# LPCB220_-_REMOTE_ACCELS.net
KiCad netlist of a schematic drawn in Altium Designer
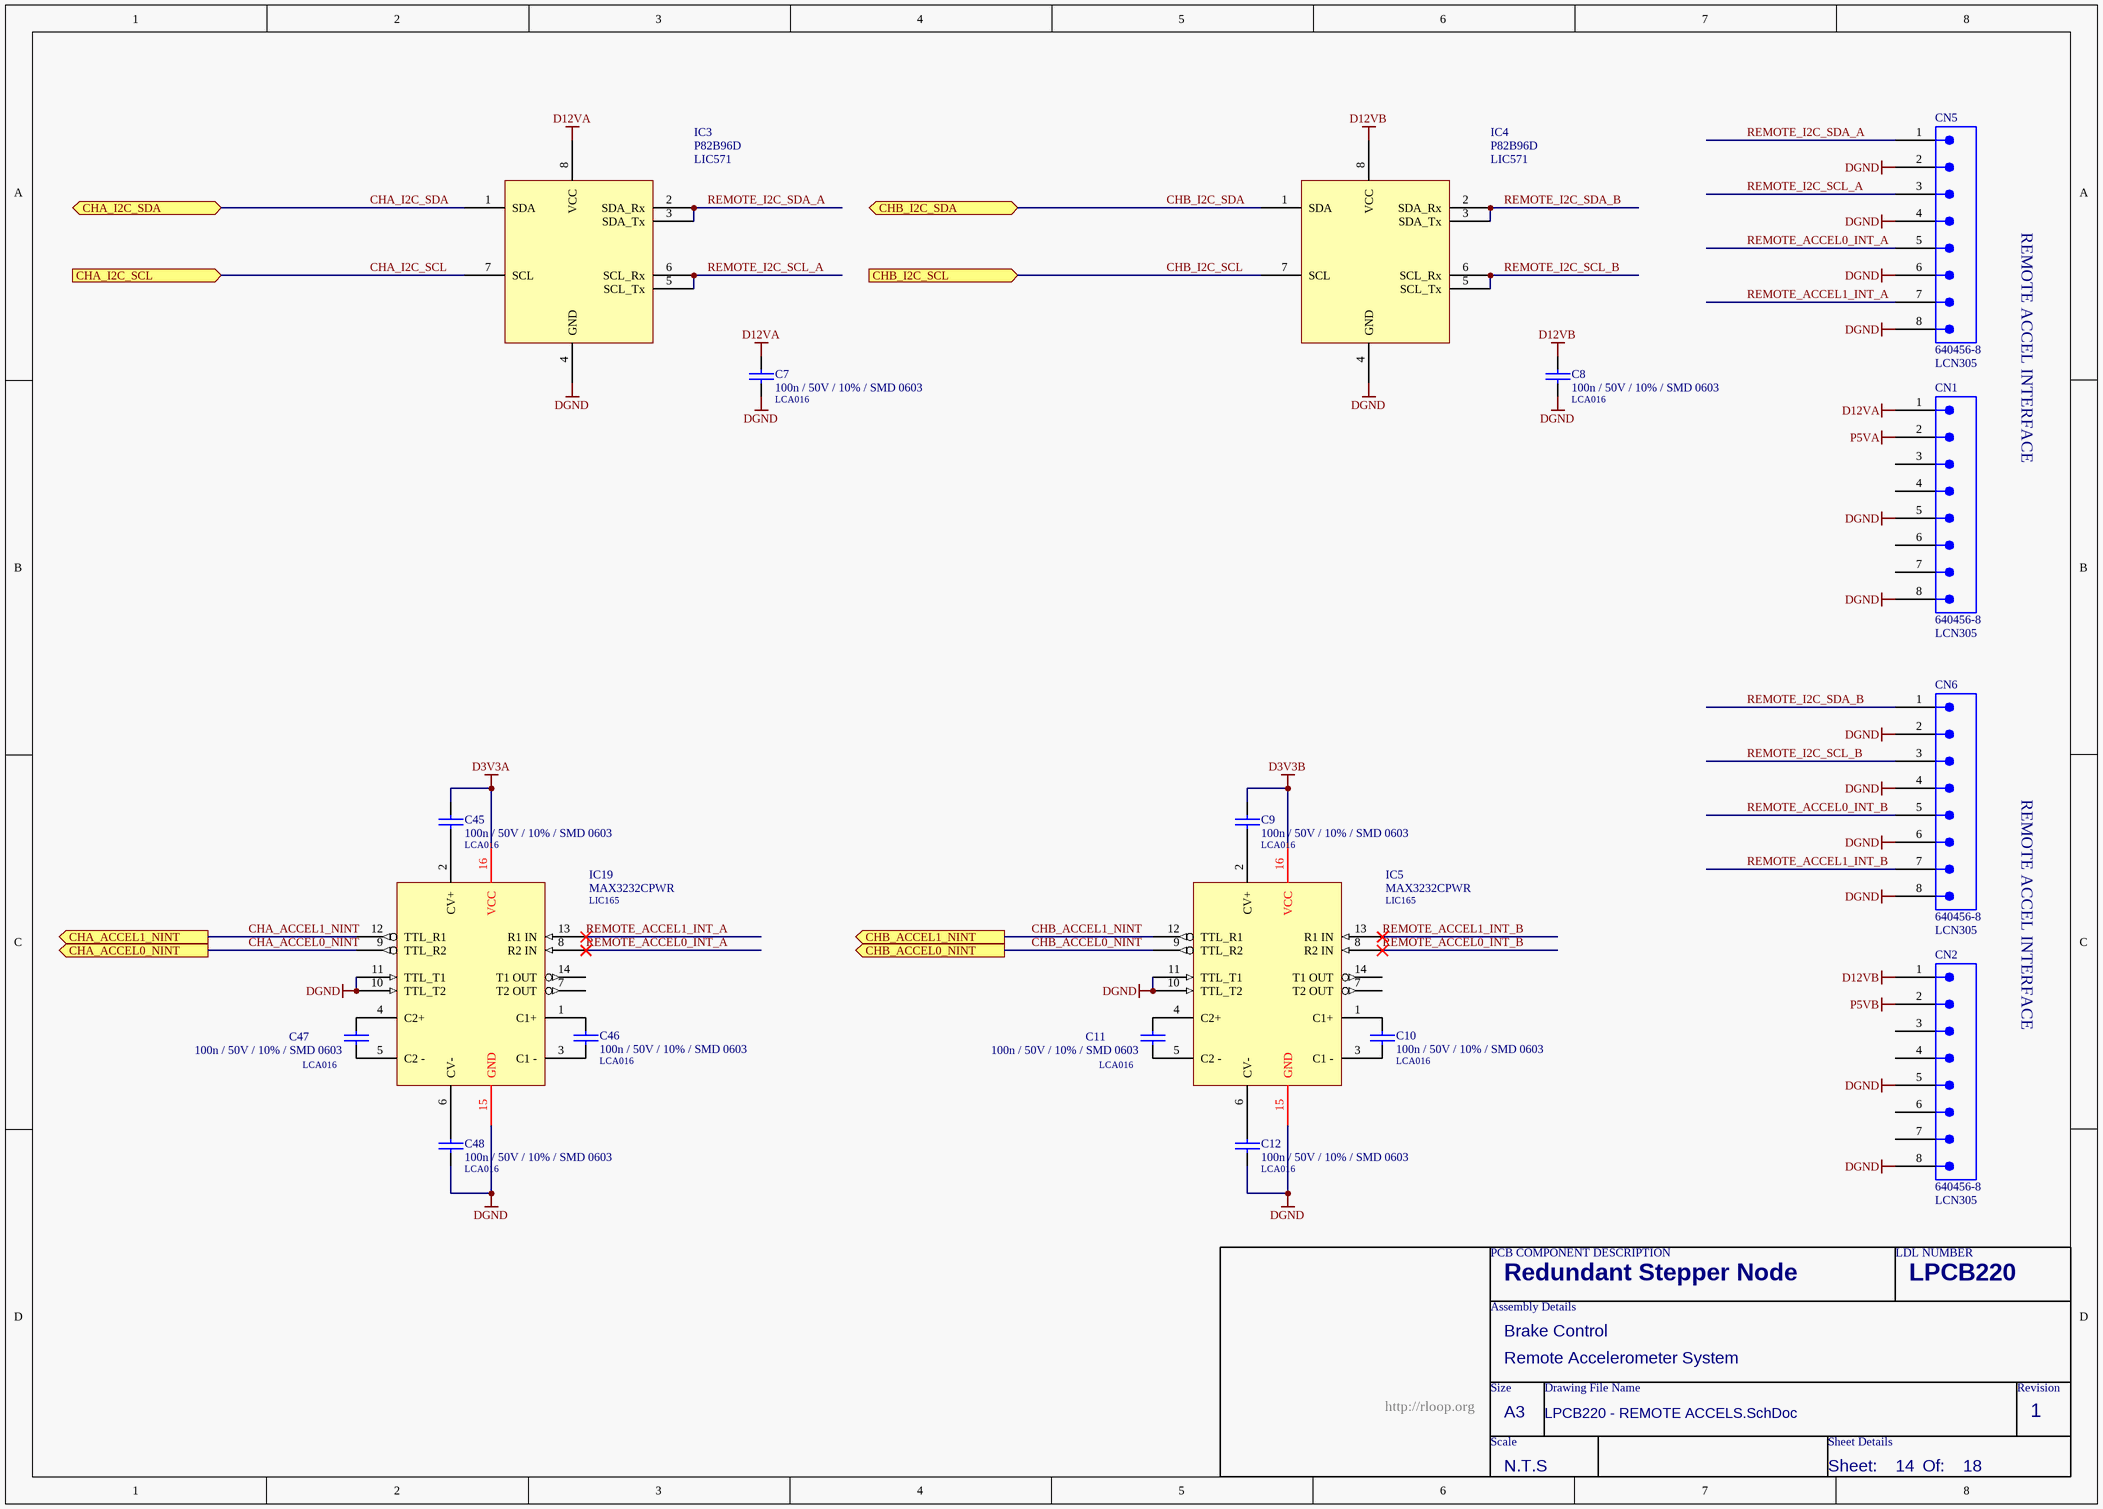
[diagram p0: LPCB220 - REMOTE ACCELS.SchDoc]

(export (version "E")
  (design (tool "Eeschema 10.0.6"))
  (components
    (comp (ref "C7")
      (value "100n / 50V / 10% / SMD 0603")
      (footprint "LFP011__CC1608-0603-IPC7351_B")
      (description "Capacitor, Ceramic Chip, 100nF (0.1uF), 50V, 5%, SMD 0603 [LCA016]")
      (fields (field (name "LDL_NUMBER") "LCA016"))
      (libsource (lib "LDL_Capacitors") (part "100n / 50V / 10% / SMD 0603"))
    )
    (comp (ref "C8")
      (value "100n / 50V / 10% / SMD 0603")
      (footprint "LFP011__CC1608-0603-IPC7351_B")
      (description "Capacitor, Ceramic Chip, 100nF (0.1uF), 50V, 5%, SMD 0603 [LCA016]")
      (fields (field (name "LDL_NUMBER") "LCA016"))
      (libsource (lib "LDL_Capacitors") (part "100n / 50V / 10% / SMD 0603"))
    )
    (comp (ref "C9")
      (value "100n / 50V / 10% / SMD 0603")
      (footprint "LFP011__CC1608-0603-IPC7351_B")
      (description "Capacitor, Ceramic Chip, 100nF, 50V, 10%, SMD 0603")
      (fields (field (name "LDL_NUMBER") "LCA016"))
      (libsource (lib "LDL_Capacitors") (part "100n / 50V / 10% / SMD 0603"))
    )
    (comp (ref "C10")
      (value "100n / 50V / 10% / SMD 0603")
      (footprint "LFP011__CC1608-0603-IPC7351_B")
      (description "Capacitor, Ceramic Chip, 100nF, 50V, 10%, SMD 0603")
      (fields (field (name "LDL_NUMBER") "LCA016"))
      (libsource (lib "LDL_Capacitors") (part "100n / 50V / 10% / SMD 0603"))
    )
    (comp (ref "C11")
      (value "100n / 50V / 10% / SMD 0603")
      (footprint "LFP011__CC1608-0603-IPC7351_B")
      (description "Capacitor, Ceramic Chip, 100nF, 50V, 10%, SMD 0603")
      (fields (field (name "LDL_NUMBER") "LCA016"))
      (libsource (lib "LDL_Capacitors") (part "100n / 50V / 10% / SMD 0603"))
    )
    (comp (ref "C12")
      (value "100n / 50V / 10% / SMD 0603")
      (footprint "LFP011__CC1608-0603-IPC7351_B")
      (description "Capacitor, Ceramic Chip, 100nF, 50V, 10%, SMD 0603")
      (fields (field (name "LDL_NUMBER") "LCA016"))
      (libsource (lib "LDL_Capacitors") (part "100n / 50V / 10% / SMD 0603"))
    )
    (comp (ref "C45")
      (value "100n / 50V / 10% / SMD 0603")
      (footprint "LFP011__CC1608-0603-IPC7351_B")
      (description "Capacitor, Ceramic Chip, 100nF, 50V, 10%, SMD 0603")
      (fields (field (name "LDL_NUMBER") "LCA016"))
      (libsource (lib "LDL_Capacitors") (part "100n / 50V / 10% / SMD 0603"))
    )
    (comp (ref "C46")
      (value "100n / 50V / 10% / SMD 0603")
      (footprint "LFP011__CC1608-0603-IPC7351_B")
      (description "Capacitor, Ceramic Chip, 100nF, 50V, 10%, SMD 0603")
      (fields (field (name "LDL_NUMBER") "LCA016"))
      (libsource (lib "LDL_Capacitors") (part "100n / 50V / 10% / SMD 0603"))
    )
    (comp (ref "C47")
      (value "100n / 50V / 10% / SMD 0603")
      (footprint "LFP011__CC1608-0603-IPC7351_B")
      (description "Capacitor, Ceramic Chip, 100nF, 50V, 10%, SMD 0603")
      (fields (field (name "LDL_NUMBER") "LCA016"))
      (libsource (lib "LDL_Capacitors") (part "100n / 50V / 10% / SMD 0603"))
    )
    (comp (ref "C48")
      (value "100n / 50V / 10% / SMD 0603")
      (footprint "LFP011__CC1608-0603-IPC7351_B")
      (description "Capacitor, Ceramic Chip, 100nF, 50V, 10%, SMD 0603")
      (fields (field (name "LDL_NUMBER") "LCA016"))
      (libsource (lib "LDL_Capacitors") (part "100n / 50V / 10% / SMD 0603"))
    )
    (comp (ref "CN1")
      (value "640456-8")
      (footprint "640456-8")
      (description "Connector, Male Header, 8 Way")
      (fields (field (name "LDL_NUMBER") "LCN305"))
      (libsource (lib "LDL_Connectors") (part "640456-8"))
    )
    (comp (ref "CN2")
      (value "640456-8")
      (footprint "640456-8")
      (description "Connector, Male Header, 8 Way")
      (fields (field (name "LDL_NUMBER") "LCN305"))
      (libsource (lib "LDL_Connectors") (part "640456-8"))
    )
    (comp (ref "CN5")
      (value "640456-8")
      (footprint "640456-8")
      (description "Connector, Male Header, 8 Way")
      (fields (field (name "LDL_NUMBER") "LCN305"))
      (libsource (lib "LDL_Connectors") (part "640456-8"))
    )
    (comp (ref "CN6")
      (value "640456-8")
      (footprint "640456-8")
      (description "Connector, Male Header, 8 Way")
      (fields (field (name "LDL_NUMBER") "LCN305"))
      (libsource (lib "LDL_Connectors") (part "640456-8"))
    )
    (comp (ref "IC3")
      (value "P82B96D")
      (footprint "LFP097__SOIC150-8")
      (description "IC, I2C Line Driver [LIC571]")
      (fields (field (name "LDL_NUMBER") "LIC571"))
      (libsource (lib "LDL_Semiconductors") (part "P82B96D"))
    )
    (comp (ref "IC4")
      (value "P82B96D")
      (footprint "LFP097__SOIC150-8")
      (description "IC, I2C Line Driver [LIC571]")
      (fields (field (name "LDL_NUMBER") "LIC571"))
      (libsource (lib "LDL_Semiconductors") (part "P82B96D"))
    )
    (comp (ref "IC5")
      (value "MAX3232CPWR")
      (footprint "LFP049__TSSOP-16")
      (description "IC, RS232 Line Driver, 3.3V, SMD TSSOP16")
      (fields (field (name "LDL_NUMBER") "LIC165"))
      (libsource (lib "LDL_Semiconductors") (part "MAX3232CPWR"))
    )
    (comp (ref "IC19")
      (value "MAX3232CPWR")
      (footprint "LFP049__TSSOP-16")
      (description "IC, RS232 Line Driver, 3.3V, SMD TSSOP16")
      (fields (field (name "LDL_NUMBER") "LIC165"))
      (libsource (lib "LDL_Semiconductors") (part "MAX3232CPWR"))
    )
  )
  (nets
    (net (code "1") (name "/CHA_ACCEL0_NINT") (class "Default")
      (node (ref "IC19") (pin "9") (pinfunction "TTL_R2_9") (pintype "output"))
    )
    (net (code "2") (name "/CHA_ACCEL1_NINT") (class "Default")
      (node (ref "IC19") (pin "12") (pinfunction "TTL_R1_12") (pintype "output"))
    )
    (net (code "3") (name "/CHA_I2C_SCL") (class "Default")
      (node (ref "IC3") (pin "7") (pinfunction "SCL_7") (pintype "passive"))
    )
    (net (code "4") (name "/CHA_I2C_SDA") (class "Default")
      (node (ref "IC3") (pin "1") (pinfunction "SDA_1") (pintype "passive"))
    )
    (net (code "5") (name "/CHB_ACCEL0_NINT") (class "Default")
      (node (ref "IC5") (pin "9") (pinfunction "TTL_R2_9") (pintype "output"))
    )
    (net (code "6") (name "/CHB_ACCEL1_NINT") (class "Default")
      (node (ref "IC5") (pin "12") (pinfunction "TTL_R1_12") (pintype "output"))
    )
    (net (code "7") (name "/CHB_I2C_SCL") (class "Default")
      (node (ref "IC4") (pin "7") (pinfunction "SCL_7") (pintype "passive"))
    )
    (net (code "8") (name "/CHB_I2C_SDA") (class "Default")
      (node (ref "IC4") (pin "1") (pinfunction "SDA_1") (pintype "passive"))
    )
    (net (code "9") (name "/REMOTE_ACCEL0_INT_A") (class "Default")
      (node (ref "CN5") (pin "5") (pinfunction "5_5") (pintype "passive"))
      (node (ref "IC19") (pin "8") (pinfunction "R2_IN_8") (pintype "input"))
    )
    (net (code "10") (name "/REMOTE_ACCEL0_INT_B") (class "Default")
      (node (ref "CN6") (pin "5") (pinfunction "5_5") (pintype "passive"))
      (node (ref "IC5") (pin "8") (pinfunction "R2_IN_8") (pintype "input"))
    )
    (net (code "11") (name "/REMOTE_ACCEL1_INT_A") (class "Default")
      (node (ref "CN5") (pin "7") (pinfunction "7_7") (pintype "passive"))
      (node (ref "IC19") (pin "13") (pinfunction "R1_IN_13") (pintype "input"))
    )
    (net (code "12") (name "/REMOTE_ACCEL1_INT_B") (class "Default")
      (node (ref "CN6") (pin "7") (pinfunction "7_7") (pintype "passive"))
      (node (ref "IC5") (pin "13") (pinfunction "R1_IN_13") (pintype "input"))
    )
    (net (code "13") (name "/REMOTE_I2C_SCL_A") (class "Default")
      (node (ref "CN5") (pin "3") (pinfunction "3_3") (pintype "passive"))
      (node (ref "IC3") (pin "5") (pinfunction "SCL_Tx_5") (pintype "passive"))
      (node (ref "IC3") (pin "6") (pinfunction "SCL_Rx_6") (pintype "passive"))
    )
    (net (code "14") (name "/REMOTE_I2C_SCL_B") (class "Default")
      (node (ref "CN6") (pin "3") (pinfunction "3_3") (pintype "passive"))
      (node (ref "IC4") (pin "5") (pinfunction "SCL_Tx_5") (pintype "passive"))
      (node (ref "IC4") (pin "6") (pinfunction "SCL_Rx_6") (pintype "passive"))
    )
    (net (code "15") (name "/REMOTE_I2C_SDA_A") (class "Default")
      (node (ref "CN5") (pin "1") (pinfunction "1_1") (pintype "passive"))
      (node (ref "IC3") (pin "2") (pinfunction "SDA_Rx_2") (pintype "passive"))
      (node (ref "IC3") (pin "3") (pinfunction "SDA_Tx_3") (pintype "passive"))
    )
    (net (code "16") (name "/REMOTE_I2C_SDA_B") (class "Default")
      (node (ref "CN6") (pin "1") (pinfunction "1_1") (pintype "passive"))
      (node (ref "IC4") (pin "2") (pinfunction "SDA_Rx_2") (pintype "passive"))
      (node (ref "IC4") (pin "3") (pinfunction "SDA_Tx_3") (pintype "passive"))
    )
    (net (code "17") (name "D3V3A") (class "Default")
      (node (ref "C45") (pin "1") (pintype "passive"))
      (node (ref "IC19") (pin "16") (pinfunction "VCC_16") (pintype "power_in"))
    )
    (net (code "18") (name "D3V3B") (class "Default")
      (node (ref "C9") (pin "1") (pintype "passive"))
      (node (ref "IC5") (pin "16") (pinfunction "VCC_16") (pintype "power_in"))
    )
    (net (code "19") (name "D12VA") (class "Default")
      (node (ref "C7") (pin "1") (pintype "passive"))
      (node (ref "CN1") (pin "1") (pinfunction "1_1") (pintype "passive"))
      (node (ref "IC3") (pin "8") (pinfunction "VCC_8") (pintype "power_in"))
    )
    (net (code "20") (name "D12VB") (class "Default")
      (node (ref "C8") (pin "1") (pintype "passive"))
      (node (ref "CN2") (pin "1") (pinfunction "1_1") (pintype "passive"))
      (node (ref "IC4") (pin "8") (pinfunction "VCC_8") (pintype "power_in"))
    )
    (net (code "21") (name "DGND") (class "Default")
      (node (ref "C12") (pin "2") (pintype "passive"))
      (node (ref "C48") (pin "2") (pintype "passive"))
      (node (ref "C7") (pin "2") (pintype "passive"))
      (node (ref "C8") (pin "2") (pintype "passive"))
      (node (ref "CN1") (pin "5") (pinfunction "5_5") (pintype "passive"))
      (node (ref "CN1") (pin "8") (pinfunction "8_8") (pintype "passive"))
      (node (ref "CN2") (pin "5") (pinfunction "5_5") (pintype "passive"))
      (node (ref "CN2") (pin "8") (pinfunction "8_8") (pintype "passive"))
      (node (ref "CN5") (pin "2") (pinfunction "2_2") (pintype "passive"))
      (node (ref "CN5") (pin "4") (pinfunction "4_4") (pintype "passive"))
      (node (ref "CN5") (pin "6") (pinfunction "6_6") (pintype "passive"))
      (node (ref "CN5") (pin "8") (pinfunction "8_8") (pintype "passive"))
      (node (ref "CN6") (pin "2") (pinfunction "2_2") (pintype "passive"))
      (node (ref "CN6") (pin "4") (pinfunction "4_4") (pintype "passive"))
      (node (ref "CN6") (pin "6") (pinfunction "6_6") (pintype "passive"))
      (node (ref "CN6") (pin "8") (pinfunction "8_8") (pintype "passive"))
      (node (ref "IC19") (pin "10") (pinfunction "TTL_T2_10") (pintype "input"))
      (node (ref "IC19") (pin "11") (pinfunction "TTL_T1_11") (pintype "input"))
      (node (ref "IC19") (pin "15") (pinfunction "GND_15") (pintype "power_in"))
      (node (ref "IC3") (pin "4") (pinfunction "GND_4") (pintype "power_in"))
      (node (ref "IC4") (pin "4") (pinfunction "GND_4") (pintype "power_in"))
      (node (ref "IC5") (pin "10") (pinfunction "TTL_T2_10") (pintype "input"))
      (node (ref "IC5") (pin "11") (pinfunction "TTL_T1_11") (pintype "input"))
      (node (ref "IC5") (pin "15") (pinfunction "GND_15") (pintype "power_in"))
    )
    (net (code "22") (name "Net-(IC5-C1+)") (class "Default")
      (node (ref "C10") (pin "1") (pintype "passive"))
      (node (ref "IC5") (pin "1") (pinfunction "C1+_1") (pintype "passive"))
    )
    (net (code "23") (name "Net-(IC5-C1_-)") (class "Default")
      (node (ref "C10") (pin "2") (pintype "passive"))
      (node (ref "IC5") (pin "3") (pinfunction "C1_-_3") (pintype "passive"))
    )
    (net (code "24") (name "Net-(IC5-C2+)") (class "Default")
      (node (ref "C11") (pin "1") (pintype "passive"))
      (node (ref "IC5") (pin "4") (pinfunction "C2+_4") (pintype "passive"))
    )
    (net (code "25") (name "Net-(IC5-C2_-)") (class "Default")
      (node (ref "C11") (pin "2") (pintype "passive"))
      (node (ref "IC5") (pin "5") (pinfunction "C2_-_5") (pintype "passive"))
    )
    (net (code "26") (name "Net-(IC5-CV+)") (class "Default")
      (node (ref "C9") (pin "2") (pintype "passive"))
      (node (ref "IC5") (pin "2") (pinfunction "CV+_2") (pintype "passive"))
    )
    (net (code "27") (name "Net-(IC5-CV-)") (class "Default")
      (node (ref "C12") (pin "1") (pintype "passive"))
      (node (ref "IC5") (pin "6") (pinfunction "CV-_6") (pintype "passive"))
    )
    (net (code "28") (name "Net-(IC19-C1+)") (class "Default")
      (node (ref "C46") (pin "1") (pintype "passive"))
      (node (ref "IC19") (pin "1") (pinfunction "C1+_1") (pintype "passive"))
    )
    (net (code "29") (name "Net-(IC19-C1_-)") (class "Default")
      (node (ref "C46") (pin "2") (pintype "passive"))
      (node (ref "IC19") (pin "3") (pinfunction "C1_-_3") (pintype "passive"))
    )
    (net (code "30") (name "Net-(IC19-C2+)") (class "Default")
      (node (ref "C47") (pin "1") (pintype "passive"))
      (node (ref "IC19") (pin "4") (pinfunction "C2+_4") (pintype "passive"))
    )
    (net (code "31") (name "Net-(IC19-C2_-)") (class "Default")
      (node (ref "C47") (pin "2") (pintype "passive"))
      (node (ref "IC19") (pin "5") (pinfunction "C2_-_5") (pintype "passive"))
    )
    (net (code "32") (name "Net-(IC19-CV+)") (class "Default")
      (node (ref "C45") (pin "2") (pintype "passive"))
      (node (ref "IC19") (pin "2") (pinfunction "CV+_2") (pintype "passive"))
    )
    (net (code "33") (name "Net-(IC19-CV-)") (class "Default")
      (node (ref "C48") (pin "1") (pintype "passive"))
      (node (ref "IC19") (pin "6") (pinfunction "CV-_6") (pintype "passive"))
    )
    (net (code "34") (name "P5VA") (class "Default")
      (node (ref "CN1") (pin "2") (pinfunction "2_2") (pintype "passive"))
    )
    (net (code "35") (name "P5VB") (class "Default")
      (node (ref "CN2") (pin "2") (pinfunction "2_2") (pintype "passive"))
    )
    (net (code "36") (name "unconnected-(CN1-Pad3)") (class "Default")
      (node (ref "CN1") (pin "3") (pinfunction "3_3") (pintype "passive"))
    )
    (net (code "37") (name "unconnected-(CN1-Pad4)") (class "Default")
      (node (ref "CN1") (pin "4") (pinfunction "4_4") (pintype "passive"))
    )
    (net (code "38") (name "unconnected-(CN1-Pad6)") (class "Default")
      (node (ref "CN1") (pin "6") (pinfunction "6_6") (pintype "passive"))
    )
    (net (code "39") (name "unconnected-(CN1-Pad7)") (class "Default")
      (node (ref "CN1") (pin "7") (pinfunction "7_7") (pintype "passive"))
    )
    (net (code "40") (name "unconnected-(CN2-Pad3)") (class "Default")
      (node (ref "CN2") (pin "3") (pinfunction "3_3") (pintype "passive"))
    )
    (net (code "41") (name "unconnected-(CN2-Pad4)") (class "Default")
      (node (ref "CN2") (pin "4") (pinfunction "4_4") (pintype "passive"))
    )
    (net (code "42") (name "unconnected-(CN2-Pad6)") (class "Default")
      (node (ref "CN2") (pin "6") (pinfunction "6_6") (pintype "passive"))
    )
    (net (code "43") (name "unconnected-(CN2-Pad7)") (class "Default")
      (node (ref "CN2") (pin "7") (pinfunction "7_7") (pintype "passive"))
    )
    (net (code "44") (name "unconnected-(IC5-T1_OUT-Pad14)") (class "Default")
      (node (ref "IC5") (pin "14") (pinfunction "T1_OUT_14") (pintype "output"))
    )
    (net (code "45") (name "unconnected-(IC5-T2_OUT-Pad7)") (class "Default")
      (node (ref "IC5") (pin "7") (pinfunction "T2_OUT_7") (pintype "output"))
    )
    (net (code "46") (name "unconnected-(IC19-T1_OUT-Pad14)") (class "Default")
      (node (ref "IC19") (pin "14") (pinfunction "T1_OUT_14") (pintype "output"))
    )
    (net (code "47") (name "unconnected-(IC19-T2_OUT-Pad7)") (class "Default")
      (node (ref "IC19") (pin "7") (pinfunction "T2_OUT_7") (pintype "output"))
    )
  )
)
